# preamp.net
KiCad netlist of a schematic drawn in EAGLE
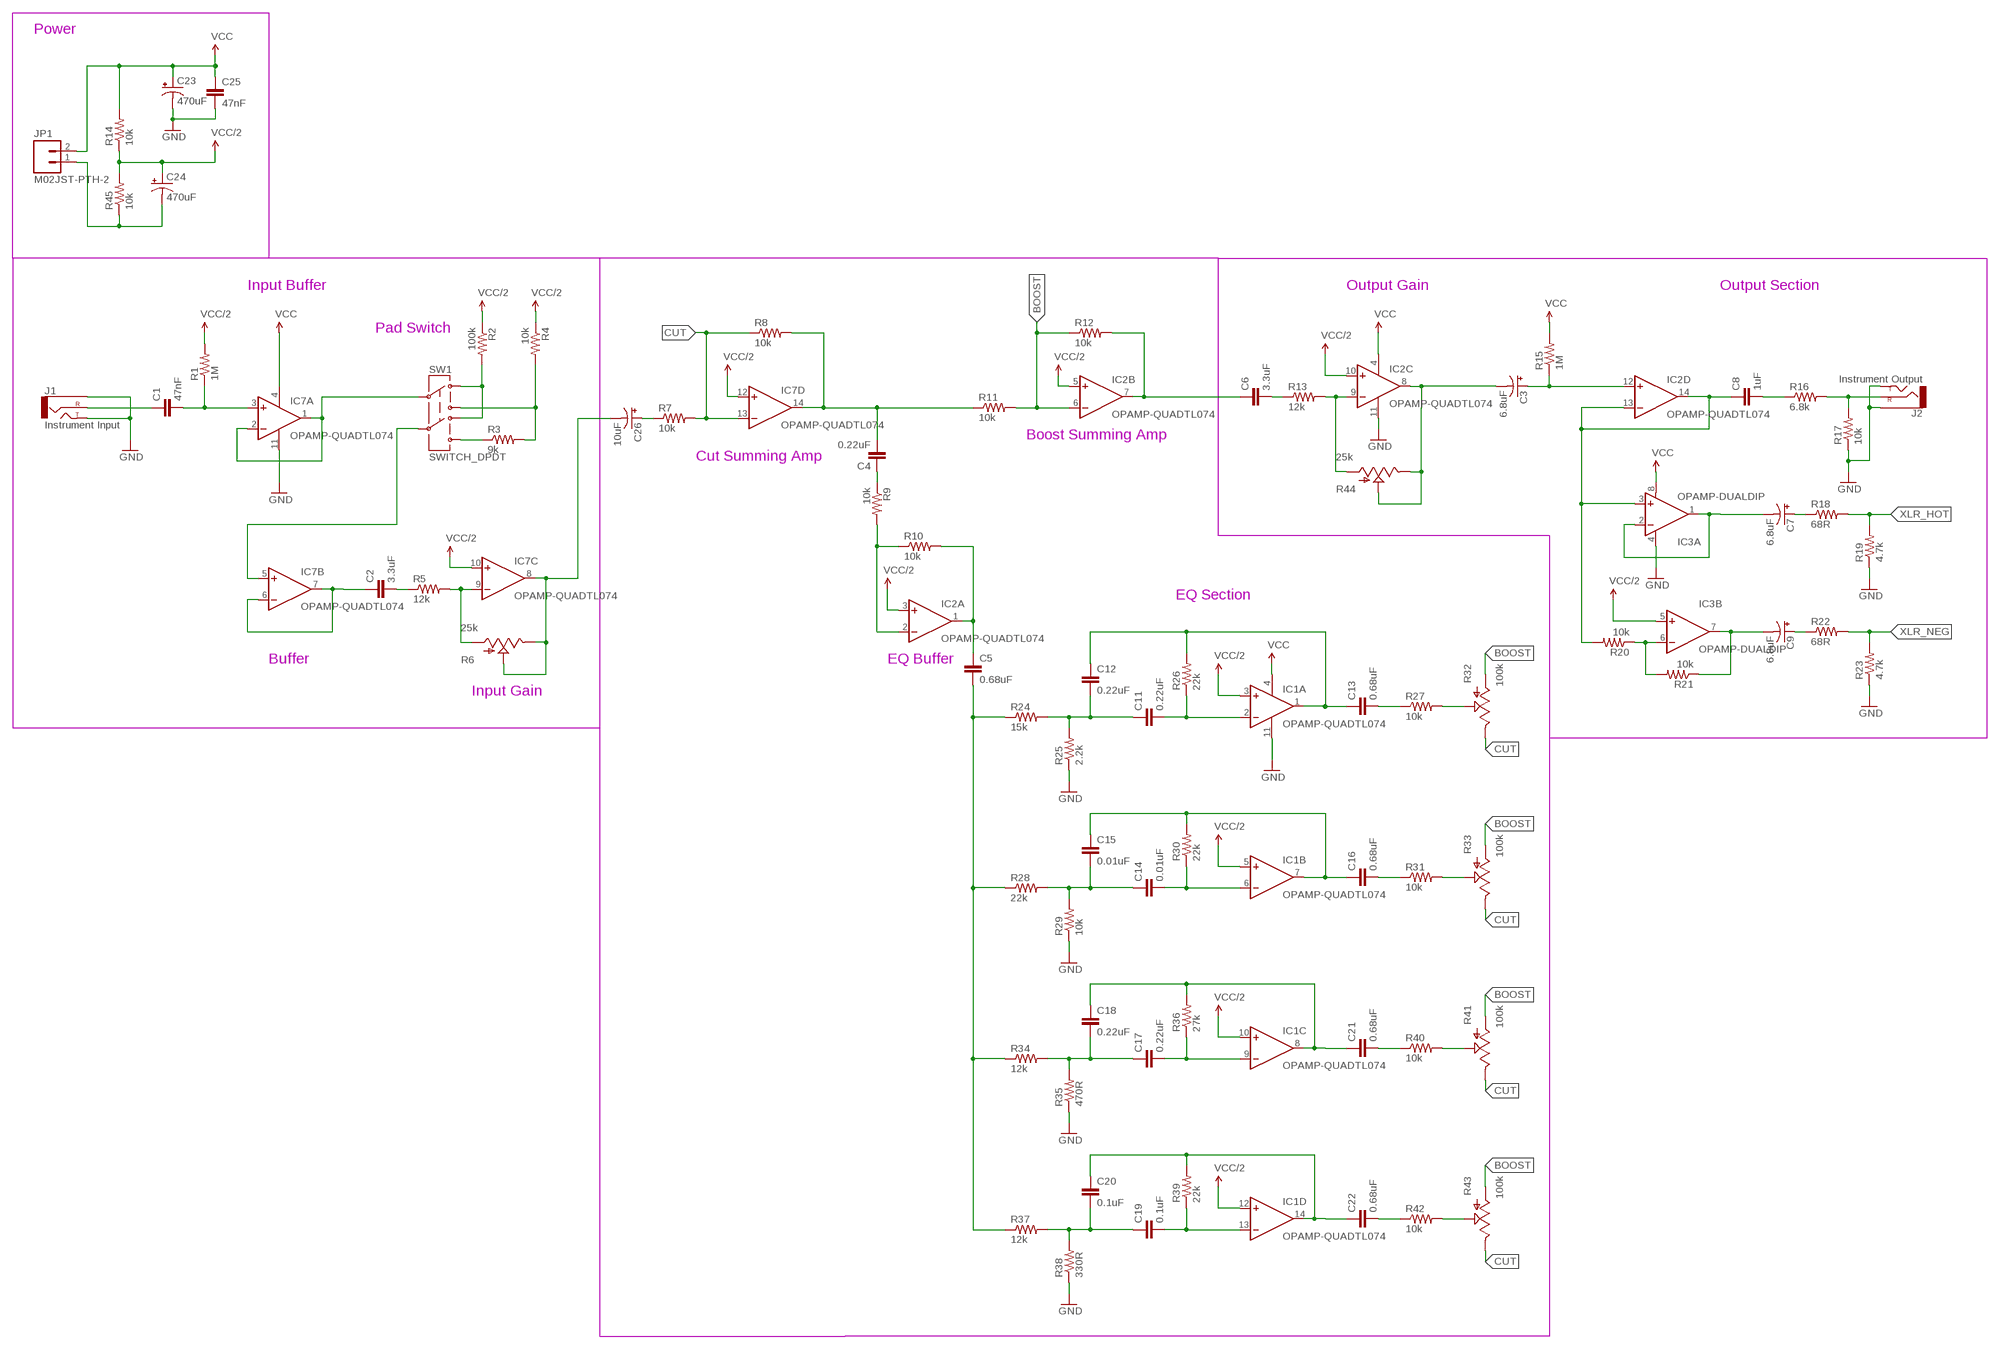
[diagram p0: schematic, sheet 1]

(export (version "E")
  (design (tool "Eeschema 10.0.6"))
  (components
    (comp (ref "C1")
      (value "47nF")
      (footprint "eagle-import:CAP-5MM")
      (fields (field (name "PARTNO") "FK28X7R1H473K"))
      (libsource (lib "eagle-import") (part "CAP"))
    )
    (comp (ref "C2")
      (value "3.3uF")
      (footprint "eagle-import:CAP-5MM")
      (fields (field (name "PARTNO") "FK28X5R1A335K"))
      (libsource (lib "eagle-import") (part "CAP"))
    )
    (comp (ref "C3")
      (value "6.8uF")
      (footprint "eagle-import:CPOL-RADIAL-10UF-25V")
      (fields (field (name "PARTNO") "ESH685M063AC3AA"))
      (libsource (lib "eagle-import") (part "CAP_POLPTH2"))
    )
    (comp (ref "C4")
      (value "0.22uF")
      (footprint "eagle-import:CAP-5MM")
      (fields (field (name "PARTNO") "FK28X7R1C224K"))
      (libsource (lib "eagle-import") (part "CAP"))
    )
    (comp (ref "C5")
      (value "0.68uF")
      (footprint "eagle-import:CAP-5MM")
      (fields (field (name "PARTNO") "FK28X5R1A684K"))
      (libsource (lib "eagle-import") (part "CAP"))
    )
    (comp (ref "C6")
      (value "3.3uF")
      (footprint "eagle-import:CAP-5MM")
      (fields (field (name "PARTNO") "FK28X5R1A335K"))
      (libsource (lib "eagle-import") (part "CAP"))
    )
    (comp (ref "C7")
      (value "6.8uF")
      (footprint "eagle-import:CPOL-RADIAL-10UF-25V")
      (fields (field (name "PARTNO") "ESH685M063AC3AA"))
      (libsource (lib "eagle-import") (part "CAP_POLPTH2"))
    )
    (comp (ref "C8")
      (value "1uF")
      (footprint "eagle-import:CAP-5MM")
      (libsource (lib "eagle-import") (part "CAP"))
    )
    (comp (ref "C9")
      (value "6.8uF")
      (footprint "eagle-import:CPOL-RADIAL-10UF-25V")
      (fields (field (name "PARTNO") "ESH685M063AC3AA"))
      (libsource (lib "eagle-import") (part "CAP_POLPTH2"))
    )
    (comp (ref "C11")
      (value "0.22uF")
      (footprint "eagle-import:CAP-5MM")
      (fields (field (name "PARTNO") "FK28X7R1C224K"))
      (libsource (lib "eagle-import") (part "CAP"))
    )
    (comp (ref "C12")
      (value "0.22uF")
      (footprint "eagle-import:CAP-5MM")
      (fields (field (name "PARTNO") "FK28X7R1C224K"))
      (libsource (lib "eagle-import") (part "CAP"))
    )
    (comp (ref "C13")
      (value "0.68uF")
      (footprint "eagle-import:CAP-5MM")
      (fields (field (name "PARTNO") "FK28X5R1A684K"))
      (libsource (lib "eagle-import") (part "CAP"))
    )
    (comp (ref "C14")
      (value "0.01uF")
      (footprint "eagle-import:CAP-5MM")
      (libsource (lib "eagle-import") (part "CAP"))
    )
    (comp (ref "C15")
      (value "0.01uF")
      (footprint "eagle-import:CAP-5MM")
      (libsource (lib "eagle-import") (part "CAP"))
    )
    (comp (ref "C16")
      (value "0.68uF")
      (footprint "eagle-import:CAP-5MM")
      (fields (field (name "PARTNO") "FK28X5R1A684K"))
      (libsource (lib "eagle-import") (part "CAP"))
    )
    (comp (ref "C17")
      (value "0.22uF")
      (footprint "eagle-import:CAP-5MM")
      (fields (field (name "PARTNO") "FK28X7R1C224K"))
      (libsource (lib "eagle-import") (part "CAP"))
    )
    (comp (ref "C18")
      (value "0.22uF")
      (footprint "eagle-import:CAP-5MM")
      (fields (field (name "PARTNO") "FK28X7R1C224K"))
      (libsource (lib "eagle-import") (part "CAP"))
    )
    (comp (ref "C19")
      (value "0.1uF")
      (footprint "eagle-import:CAP-5MM")
      (libsource (lib "eagle-import") (part "CAP"))
    )
    (comp (ref "C20")
      (value "0.1uF")
      (footprint "eagle-import:CAP-5MM")
      (libsource (lib "eagle-import") (part "CAP"))
    )
    (comp (ref "C21")
      (value "0.68uF")
      (footprint "eagle-import:CAP-5MM")
      (fields (field (name "PARTNO") "FK28X5R1A684K"))
      (libsource (lib "eagle-import") (part "CAP"))
    )
    (comp (ref "C22")
      (value "0.68uF")
      (footprint "eagle-import:CAP-5MM")
      (fields (field (name "PARTNO") "FK28X5R1A684K"))
      (libsource (lib "eagle-import") (part "CAP"))
    )
    (comp (ref "C23")
      (value "470uF")
      (footprint "eagle-import:CPOL-RADIAL-100UF-25V")
      (libsource (lib "eagle-import") (part "SparkFun-Passives_CAP_POLPTH1"))
    )
    (comp (ref "C24")
      (value "470uF")
      (footprint "eagle-import:CPOL-RADIAL-100UF-25V")
      (libsource (lib "eagle-import") (part "SparkFun-Passives_CAP_POLPTH1"))
    )
    (comp (ref "C25")
      (value "47nF")
      (footprint "eagle-import:CAP-5MM")
      (fields (field (name "PARTNO") "FK28X7R1H473K"))
      (libsource (lib "eagle-import") (part "CAP"))
    )
    (comp (ref "C26")
      (value "10uF")
      (footprint "eagle-import:CPOL-RADIAL-10UF-25V")
      (libsource (lib "eagle-import") (part "CAP_POLPTH2"))
    )
    (comp (ref "IC1")
      (value "OPAMP-QUADTL074")
      (footprint "eagle-import:DIP14")
      (fields (field (name "PARTNO") "TL074CN"))
      (libsource (lib "eagle-import") (part "OPAMP-QUADTL074"))
    )
    (comp (ref "IC2")
      (value "OPAMP-QUADTL074")
      (footprint "eagle-import:DIP14")
      (fields (field (name "PARTNO") "TL074CN"))
      (libsource (lib "eagle-import") (part "OPAMP-QUADTL074"))
    )
    (comp (ref "IC3")
      (value "OPAMP-DUALDIP")
      (footprint "eagle-import:DIP08")
      (fields (field (name "PARTNO") "TL072IP"))
      (libsource (lib "eagle-import") (part "OPAMP-DUALDIP"))
    )
    (comp (ref "IC7")
      (value "OPAMP-QUADTL074")
      (footprint "eagle-import:DIP14")
      (fields (field (name "PARTNO") "TL074CN"))
      (libsource (lib "eagle-import") (part "OPAMP-QUADTL074"))
    )
    (comp (ref "J1")
      (value "Instrument Input")
      (footprint "eagle-import:AUDIO-JACK-RA49B12B")
      (libsource (lib "eagle-import") (part "AUDIO-JACK"))
    )
    (comp (ref "J2")
      (value "Instrument Output")
      (footprint "eagle-import:AUDIO-JACK-RA49B12B")
      (libsource (lib "eagle-import") (part "AUDIO-JACK"))
    )
    (comp (ref "JP1")
      (value "M02JST-PTH-2")
      (footprint "eagle-import:JST-2-PTH")
      (libsource (lib "eagle-import") (part "M02JST-PTH-2"))
    )
    (comp (ref "R1")
      (value "1M")
      (footprint "eagle-import:AXIAL-0.4")
      (fields (field (name "PARTNO") "CF14JT1M00"))
      (libsource (lib "eagle-import") (part "RESISTORPTH-1/4W"))
    )
    (comp (ref "R2")
      (value "100k")
      (footprint "eagle-import:AXIAL-0.4")
      (fields (field (name "PARTNO") "CF14JT100K"))
      (libsource (lib "eagle-import") (part "RESISTORPTH-1/4W"))
    )
    (comp (ref "R3")
      (value "9k")
      (footprint "eagle-import:AXIAL-0.4")
      (fields (field (name "PARTNO") "CF14JT9K10"))
      (libsource (lib "eagle-import") (part "RESISTORPTH-1/4W"))
    )
    (comp (ref "R4")
      (value "10k")
      (footprint "eagle-import:AXIAL-0.4")
      (fields (field (name "PARTNO") "CF14JT10K0"))
      (libsource (lib "eagle-import") (part "RESISTORPTH-1/4W"))
    )
    (comp (ref "R5")
      (value "12k")
      (footprint "eagle-import:AXIAL-0.4")
      (fields (field (name "PARTNO") "CF14JT12K0"))
      (libsource (lib "eagle-import") (part "RESISTORPTH-1/4W"))
    )
    (comp (ref "R6")
      (value "25k")
      (footprint "eagle-import:POTENTIOMETER-EVUE2A")
      (fields (field (name "PARTNO") "EVU-E2AF25D24"))
      (libsource (lib "eagle-import") (part "POTPANA"))
    )
    (comp (ref "R7")
      (value "10k")
      (footprint "eagle-import:AXIAL-0.4")
      (fields (field (name "PARTNO") "CF14JT10K0"))
      (libsource (lib "eagle-import") (part "RESISTORPTH-1/4W"))
    )
    (comp (ref "R8")
      (value "10k")
      (footprint "eagle-import:AXIAL-0.4")
      (fields (field (name "PARTNO") "CF14JT10K0"))
      (libsource (lib "eagle-import") (part "RESISTORPTH-1/4W"))
    )
    (comp (ref "R9")
      (value "10k")
      (footprint "eagle-import:AXIAL-0.4")
      (fields (field (name "PARTNO") "CF14JT10K0"))
      (libsource (lib "eagle-import") (part "RESISTORPTH-1/4W"))
    )
    (comp (ref "R10")
      (value "10k")
      (footprint "eagle-import:AXIAL-0.4")
      (fields (field (name "PARTNO") "CF14JT10K0"))
      (libsource (lib "eagle-import") (part "RESISTORPTH-1/4W"))
    )
    (comp (ref "R11")
      (value "10k")
      (footprint "eagle-import:AXIAL-0.4")
      (fields (field (name "PARTNO") "CF14JT10K0"))
      (libsource (lib "eagle-import") (part "RESISTORPTH-1/4W"))
    )
    (comp (ref "R12")
      (value "10k")
      (footprint "eagle-import:AXIAL-0.4")
      (fields (field (name "PARTNO") "CF14JT10K0"))
      (libsource (lib "eagle-import") (part "RESISTORPTH-1/4W"))
    )
    (comp (ref "R13")
      (value "12k")
      (footprint "eagle-import:AXIAL-0.4")
      (fields (field (name "PARTNO") "CF14JT12K0"))
      (libsource (lib "eagle-import") (part "RESISTORPTH-1/4W"))
    )
    (comp (ref "R14")
      (value "10k")
      (footprint "eagle-import:AXIAL-0.4")
      (fields (field (name "PARTNO") "CF14JT10K0"))
      (libsource (lib "eagle-import") (part "RESISTORPTH-1/4W"))
    )
    (comp (ref "R15")
      (value "1M")
      (footprint "eagle-import:AXIAL-0.4")
      (fields (field (name "PARTNO") "CF14JT1M00"))
      (libsource (lib "eagle-import") (part "RESISTORPTH-1/4W"))
    )
    (comp (ref "R16")
      (value "6.8k")
      (footprint "eagle-import:AXIAL-0.4")
      (fields (field (name "PARTNO") "CF14JT6K80"))
      (libsource (lib "eagle-import") (part "RESISTORPTH-1/4W"))
    )
    (comp (ref "R17")
      (value "10k")
      (footprint "eagle-import:AXIAL-0.4")
      (fields (field (name "PARTNO") "CF14JT10K0"))
      (libsource (lib "eagle-import") (part "RESISTORPTH-1/4W"))
    )
    (comp (ref "R18")
      (value "68R")
      (footprint "eagle-import:AXIAL-0.4")
      (fields (field (name "PARTNO") "CF14JT68R0"))
      (libsource (lib "eagle-import") (part "RESISTORPTH-1/4W"))
    )
    (comp (ref "R19")
      (value "4.7k")
      (footprint "eagle-import:AXIAL-0.4")
      (fields (field (name "PARTNO") "CF14JT4K70"))
      (libsource (lib "eagle-import") (part "RESISTORPTH-1/4W"))
    )
    (comp (ref "R20")
      (value "10k")
      (footprint "eagle-import:AXIAL-0.4")
      (fields (field (name "PARTNO") "CF14JT10K0"))
      (libsource (lib "eagle-import") (part "RESISTORPTH-1/4W"))
    )
    (comp (ref "R21")
      (value "10k")
      (footprint "eagle-import:AXIAL-0.4")
      (fields (field (name "PARTNO") "CF14JT10K0"))
      (libsource (lib "eagle-import") (part "RESISTORPTH-1/4W"))
    )
    (comp (ref "R22")
      (value "68R")
      (footprint "eagle-import:AXIAL-0.4")
      (fields (field (name "PARTNO") "CF14JT68R0"))
      (libsource (lib "eagle-import") (part "RESISTORPTH-1/4W"))
    )
    (comp (ref "R23")
      (value "4.7k")
      (footprint "eagle-import:AXIAL-0.4")
      (fields (field (name "PARTNO") "CF14JT4K70"))
      (libsource (lib "eagle-import") (part "RESISTORPTH-1/4W"))
    )
    (comp (ref "R24")
      (value "15k")
      (footprint "eagle-import:AXIAL-0.4")
      (fields (field (name "PARTNO") "CF14JT15K0"))
      (libsource (lib "eagle-import") (part "RESISTORPTH-1/4W"))
    )
    (comp (ref "R25")
      (value "2.2k")
      (footprint "eagle-import:AXIAL-0.4")
      (fields (field (name "PARTNO") "CF14JT2K20"))
      (libsource (lib "eagle-import") (part "RESISTORPTH-1/4W"))
    )
    (comp (ref "R26")
      (value "22k")
      (footprint "eagle-import:AXIAL-0.4")
      (fields (field (name "PARTNO") "CF14JT22K0"))
      (libsource (lib "eagle-import") (part "RESISTORPTH-1/4W"))
    )
    (comp (ref "R27")
      (value "10k")
      (footprint "eagle-import:AXIAL-0.4")
      (fields (field (name "PARTNO") "CF14JT10K0"))
      (libsource (lib "eagle-import") (part "RESISTORPTH-1/4W"))
    )
    (comp (ref "R28")
      (value "22k")
      (footprint "eagle-import:AXIAL-0.4")
      (fields (field (name "PARTNO") "CF14JT22K0"))
      (libsource (lib "eagle-import") (part "RESISTORPTH-1/4W"))
    )
    (comp (ref "R29")
      (value "10k")
      (footprint "eagle-import:AXIAL-0.4")
      (fields (field (name "PARTNO") "CF14JT10K0"))
      (libsource (lib "eagle-import") (part "RESISTORPTH-1/4W"))
    )
    (comp (ref "R30")
      (value "22k")
      (footprint "eagle-import:AXIAL-0.4")
      (fields (field (name "PARTNO") "CF14JT22K0"))
      (libsource (lib "eagle-import") (part "RESISTORPTH-1/4W"))
    )
    (comp (ref "R31")
      (value "10k")
      (footprint "eagle-import:AXIAL-0.4")
      (fields (field (name "PARTNO") "CF14JT10K0"))
      (libsource (lib "eagle-import") (part "RESISTORPTH-1/4W"))
    )
    (comp (ref "R32")
      (value "100k")
      (footprint "eagle-import:POTENTIOMETER-PTV09A-2020F-B104")
      (fields (field (name "PARTNO") "PTV09A-2020F-B104"))
      (libsource (lib "eagle-import") (part "POTBOURNS"))
    )
    (comp (ref "R33")
      (value "100k")
      (footprint "eagle-import:POTENTIOMETER-PTV09A-2020F-B104")
      (fields (field (name "PARTNO") "PTV09A-2020F-B104"))
      (libsource (lib "eagle-import") (part "POTBOURNS"))
    )
    (comp (ref "R34")
      (value "12k")
      (footprint "eagle-import:AXIAL-0.4")
      (fields (field (name "PARTNO") "CF14JT12K0"))
      (libsource (lib "eagle-import") (part "RESISTORPTH-1/4W"))
    )
    (comp (ref "R35")
      (value "470R")
      (footprint "eagle-import:AXIAL-0.4")
      (libsource (lib "eagle-import") (part "RESISTORPTH-1/4W"))
    )
    (comp (ref "R36")
      (value "27k")
      (footprint "eagle-import:AXIAL-0.4")
      (libsource (lib "eagle-import") (part "RESISTORPTH-1/4W"))
    )
    (comp (ref "R37")
      (value "12k")
      (footprint "eagle-import:AXIAL-0.4")
      (fields (field (name "PARTNO") "CF14JT12K0"))
      (libsource (lib "eagle-import") (part "RESISTORPTH-1/4W"))
    )
    (comp (ref "R38")
      (value "330R")
      (footprint "eagle-import:AXIAL-0.4")
      (libsource (lib "eagle-import") (part "RESISTORPTH-1/4W"))
    )
    (comp (ref "R39")
      (value "22k")
      (footprint "eagle-import:AXIAL-0.4")
      (fields (field (name "PARTNO") "CF14JT22K0"))
      (libsource (lib "eagle-import") (part "RESISTORPTH-1/4W"))
    )
    (comp (ref "R40")
      (value "10k")
      (footprint "eagle-import:AXIAL-0.4")
      (fields (field (name "PARTNO") "CF14JT10K0"))
      (libsource (lib "eagle-import") (part "RESISTORPTH-1/4W"))
    )
    (comp (ref "R41")
      (value "100k")
      (footprint "eagle-import:POTENTIOMETER-PTV09A-2020F-B104")
      (fields (field (name "PARTNO") "PTV09A-2020F-B104"))
      (libsource (lib "eagle-import") (part "POTBOURNS"))
    )
    (comp (ref "R42")
      (value "10k")
      (footprint "eagle-import:AXIAL-0.4")
      (fields (field (name "PARTNO") "CF14JT10K0"))
      (libsource (lib "eagle-import") (part "RESISTORPTH-1/4W"))
    )
    (comp (ref "R43")
      (value "100k")
      (footprint "eagle-import:POTENTIOMETER-PTV09A-2020F-B104")
      (fields (field (name "PARTNO") "PTV09A-2020F-B104"))
      (libsource (lib "eagle-import") (part "POTBOURNS"))
    )
    (comp (ref "R44")
      (value "25k")
      (footprint "eagle-import:POTENTIOMETER-EVUE2A")
      (fields (field (name "PARTNO") "EVU-E2AF25D24"))
      (libsource (lib "eagle-import") (part "POTPANA"))
    )
    (comp (ref "R45")
      (value "10k")
      (footprint "eagle-import:AXIAL-0.4")
      (fields (field (name "PARTNO") "CF14JT10K0"))
      (libsource (lib "eagle-import") (part "RESISTORPTH-1/4W"))
    )
    (comp (ref "SW1")
      (value "SWITCH_DPDT")
      (footprint "eagle-import:SWITCH-EG2211")
      (libsource (lib "eagle-import") (part "SWITCH_DPDT"))
    )
  )
  (nets
    (net (code "1") (name "BOOST") (class "Default")
      (node (ref "IC2") (pin "6") (pinfunction "IN-_6") (pintype "input"))
      (node (ref "R11") (pin "P$2") (pinfunction "2_P$2") (pintype "passive"))
      (node (ref "R12") (pin "P$1") (pinfunction "1_P$1") (pintype "passive"))
      (node (ref "R32") (pin "3") (pinfunction "A_3") (pintype "passive"))
      (node (ref "R33") (pin "3") (pinfunction "A_3") (pintype "passive"))
      (node (ref "R41") (pin "3") (pinfunction "A_3") (pintype "passive"))
      (node (ref "R43") (pin "3") (pinfunction "A_3") (pintype "passive"))
    )
    (net (code "2") (name "CUT") (class "Default")
      (node (ref "IC7") (pin "13") (pinfunction "IN-_13") (pintype "input"))
      (node (ref "R32") (pin "1") (pinfunction "E_1") (pintype "passive"))
      (node (ref "R33") (pin "1") (pinfunction "E_1") (pintype "passive"))
      (node (ref "R41") (pin "1") (pinfunction "E_1") (pintype "passive"))
      (node (ref "R43") (pin "1") (pinfunction "E_1") (pintype "passive"))
      (node (ref "R7") (pin "P$2") (pinfunction "2_P$2") (pintype "passive"))
      (node (ref "R8") (pin "P$1") (pinfunction "1_P$1") (pintype "passive"))
    )
    (net (code "3") (name "GND") (class "Default")
      (node (ref "C23") (pin "2") (pinfunction "-_2") (pintype "passive"))
      (node (ref "C25") (pin "2") (pinfunction "2_2") (pintype "passive"))
      (node (ref "IC1") (pin "11") (pinfunction "VEE_11") (pintype "power_in"))
      (node (ref "IC2") (pin "11") (pinfunction "VEE_11") (pintype "power_in"))
      (node (ref "IC3") (pin "4") (pinfunction "V-_4") (pintype "power_in"))
      (node (ref "IC7") (pin "11") (pinfunction "VEE_11") (pintype "power_in"))
      (node (ref "J1") (pin "S") (pinfunction "SLEEVE_S") (pintype "bidirectional"))
      (node (ref "J1") (pin "T") (pinfunction "TIP_T") (pintype "bidirectional"))
      (node (ref "J2") (pin "S") (pinfunction "SLEEVE_S") (pintype "bidirectional"))
      (node (ref "J2") (pin "T") (pinfunction "TIP_T") (pintype "bidirectional"))
      (node (ref "R17") (pin "P$1") (pinfunction "1_P$1") (pintype "passive"))
      (node (ref "R19") (pin "P$1") (pinfunction "1_P$1") (pintype "passive"))
      (node (ref "R23") (pin "P$1") (pinfunction "1_P$1") (pintype "passive"))
      (node (ref "R25") (pin "P$1") (pinfunction "1_P$1") (pintype "passive"))
      (node (ref "R29") (pin "P$1") (pinfunction "1_P$1") (pintype "passive"))
      (node (ref "R35") (pin "P$1") (pinfunction "1_P$1") (pintype "passive"))
      (node (ref "R38") (pin "P$1") (pinfunction "1_P$1") (pintype "passive"))
    )
    (net (code "4") (name "Net-(C3-+)") (class "Default")
      (node (ref "C3") (pin "1") (pinfunction "+_1") (pintype "passive"))
      (node (ref "IC2") (pin "12") (pinfunction "IN+_12") (pintype "input"))
      (node (ref "R15") (pin "P$1") (pinfunction "1_P$1") (pintype "passive"))
    )
    (net (code "5") (name "Net-(C3--)") (class "Default")
      (node (ref "C3") (pin "2") (pinfunction "-_2") (pintype "passive"))
      (node (ref "IC2") (pin "8") (pinfunction "OUT_8") (pintype "output"))
      (node (ref "R44") (pin "2") (pinfunction "S_2") (pintype "passive"))
      (node (ref "R44") (pin "3") (pinfunction "E_3") (pintype "passive"))
    )
    (net (code "6") (name "Net-(C7-+)") (class "Default")
      (node (ref "C7") (pin "1") (pinfunction "+_1") (pintype "passive"))
      (node (ref "R18") (pin "P$1") (pinfunction "1_P$1") (pintype "passive"))
    )
    (net (code "7") (name "Net-(C7--)") (class "Default")
      (node (ref "C7") (pin "2") (pinfunction "-_2") (pintype "passive"))
      (node (ref "IC3") (pin "1") (pinfunction "OUT_1") (pintype "output"))
      (node (ref "IC3") (pin "2") (pinfunction "-IN_2") (pintype "input"))
    )
    (net (code "8") (name "Net-(C9-+)") (class "Default")
      (node (ref "C9") (pin "1") (pinfunction "+_1") (pintype "passive"))
      (node (ref "R22") (pin "P$1") (pinfunction "1_P$1") (pintype "passive"))
    )
    (net (code "9") (name "Net-(C9--)") (class "Default")
      (node (ref "C9") (pin "2") (pinfunction "-_2") (pintype "passive"))
      (node (ref "IC3") (pin "7") (pinfunction "OUT_7") (pintype "output"))
      (node (ref "R21") (pin "P$1") (pinfunction "1_P$1") (pintype "passive"))
    )
    (net (code "10") (name "Net-(C24--)") (class "Default")
      (node (ref "C24") (pin "2") (pinfunction "-_2") (pintype "passive"))
      (node (ref "JP1") (pin "1") (pinfunction "1_1") (pintype "passive"))
      (node (ref "R45") (pin "P$1") (pinfunction "1_P$1") (pintype "passive"))
    )
    (net (code "11") (name "Net-(C26-+)") (class "Default")
      (node (ref "C26") (pin "1") (pinfunction "+_1") (pintype "passive"))
      (node (ref "R7") (pin "P$1") (pinfunction "1_P$1") (pintype "passive"))
    )
    (net (code "12") (name "Net-(C26--)") (class "Default")
      (node (ref "C26") (pin "2") (pinfunction "-_2") (pintype "passive"))
      (node (ref "IC7") (pin "8") (pinfunction "OUT_8") (pintype "output"))
      (node (ref "R6") (pin "2") (pinfunction "S_2") (pintype "passive"))
      (node (ref "R6") (pin "3") (pinfunction "E_3") (pintype "passive"))
    )
    (net (code "13") (name "Net-(IC1A-IN-)") (class "Default")
      (node (ref "C11") (pin "2") (pinfunction "2_2") (pintype "passive"))
      (node (ref "IC1") (pin "2") (pinfunction "IN-_2") (pintype "input"))
      (node (ref "R26") (pin "P$1") (pinfunction "1_P$1") (pintype "passive"))
    )
    (net (code "14") (name "Net-(IC1A-OUT)") (class "Default")
      (node (ref "C12") (pin "1") (pinfunction "1_1") (pintype "passive"))
      (node (ref "C13") (pin "1") (pinfunction "1_1") (pintype "passive"))
      (node (ref "IC1") (pin "1") (pinfunction "OUT_1") (pintype "output"))
      (node (ref "R26") (pin "P$2") (pinfunction "2_P$2") (pintype "passive"))
    )
    (net (code "15") (name "Net-(IC1B-IN-)") (class "Default")
      (node (ref "C14") (pin "2") (pinfunction "2_2") (pintype "passive"))
      (node (ref "IC1") (pin "6") (pinfunction "IN-_6") (pintype "input"))
      (node (ref "R30") (pin "P$1") (pinfunction "1_P$1") (pintype "passive"))
    )
    (net (code "16") (name "Net-(IC1B-OUT)") (class "Default")
      (node (ref "C15") (pin "1") (pinfunction "1_1") (pintype "passive"))
      (node (ref "C16") (pin "1") (pinfunction "1_1") (pintype "passive"))
      (node (ref "IC1") (pin "7") (pinfunction "OUT_7") (pintype "output"))
      (node (ref "R30") (pin "P$2") (pinfunction "2_P$2") (pintype "passive"))
    )
    (net (code "17") (name "Net-(IC1C-IN-)") (class "Default")
      (node (ref "C17") (pin "2") (pinfunction "2_2") (pintype "passive"))
      (node (ref "IC1") (pin "9") (pinfunction "IN-_9") (pintype "input"))
      (node (ref "R36") (pin "P$1") (pinfunction "1_P$1") (pintype "passive"))
    )
    (net (code "18") (name "Net-(IC1C-OUT)") (class "Default")
      (node (ref "C18") (pin "1") (pinfunction "1_1") (pintype "passive"))
      (node (ref "C21") (pin "1") (pinfunction "1_1") (pintype "passive"))
      (node (ref "IC1") (pin "8") (pinfunction "OUT_8") (pintype "output"))
      (node (ref "R36") (pin "P$2") (pinfunction "2_P$2") (pintype "passive"))
    )
    (net (code "19") (name "Net-(IC1D-IN-)") (class "Default")
      (node (ref "C19") (pin "2") (pinfunction "2_2") (pintype "passive"))
      (node (ref "IC1") (pin "13") (pinfunction "IN-_13") (pintype "input"))
      (node (ref "R39") (pin "P$1") (pinfunction "1_P$1") (pintype "passive"))
    )
    (net (code "20") (name "Net-(IC1D-OUT)") (class "Default")
      (node (ref "C20") (pin "1") (pinfunction "1_1") (pintype "passive"))
      (node (ref "C22") (pin "1") (pinfunction "1_1") (pintype "passive"))
      (node (ref "IC1") (pin "14") (pinfunction "OUT_14") (pintype "output"))
      (node (ref "R39") (pin "P$2") (pinfunction "2_P$2") (pintype "passive"))
    )
    (net (code "21") (name "Net-(IC2A-IN-)") (class "Default")
      (node (ref "IC2") (pin "2") (pinfunction "IN-_2") (pintype "input"))
      (node (ref "R10") (pin "P$1") (pinfunction "1_P$1") (pintype "passive"))
      (node (ref "R9") (pin "P$2") (pinfunction "2_P$2") (pintype "passive"))
    )
    (net (code "22") (name "Net-(IC2A-OUT)") (class "Default")
      (node (ref "C5") (pin "1") (pinfunction "1_1") (pintype "passive"))
      (node (ref "IC2") (pin "1") (pinfunction "OUT_1") (pintype "output"))
      (node (ref "R10") (pin "P$2") (pinfunction "2_P$2") (pintype "passive"))
    )
    (net (code "23") (name "Net-(IC2B-OUT)") (class "Default")
      (node (ref "C6") (pin "1") (pinfunction "1_1") (pintype "passive"))
      (node (ref "IC2") (pin "7") (pinfunction "OUT_7") (pintype "output"))
      (node (ref "R12") (pin "P$2") (pinfunction "2_P$2") (pintype "passive"))
    )
    (net (code "24") (name "Net-(IC2C-IN-)") (class "Default")
      (node (ref "IC2") (pin "9") (pinfunction "IN-_9") (pintype "input"))
      (node (ref "R13") (pin "P$2") (pinfunction "2_P$2") (pintype "passive"))
      (node (ref "R44") (pin "1") (pinfunction "A_1") (pintype "passive"))
    )
    (net (code "25") (name "Net-(IC2D-IN-)") (class "Default")
      (node (ref "C8") (pin "1") (pinfunction "1_1") (pintype "passive"))
      (node (ref "IC2") (pin "13") (pinfunction "IN-_13") (pintype "input"))
      (node (ref "IC2") (pin "14") (pinfunction "OUT_14") (pintype "output"))
      (node (ref "IC3") (pin "3") (pinfunction "+IN_3") (pintype "input"))
      (node (ref "R20") (pin "P$2") (pinfunction "2_P$2") (pintype "passive"))
    )
    (net (code "26") (name "Net-(IC3B--IN)") (class "Default")
      (node (ref "IC3") (pin "6") (pinfunction "-IN_6") (pintype "input"))
      (node (ref "R20") (pin "P$1") (pinfunction "1_P$1") (pintype "passive"))
      (node (ref "R21") (pin "P$2") (pinfunction "2_P$2") (pintype "passive"))
    )
    (net (code "27") (name "Net-(IC7A-IN+)") (class "Default")
      (node (ref "C1") (pin "2") (pinfunction "2_2") (pintype "passive"))
      (node (ref "IC7") (pin "3") (pinfunction "IN+_3") (pintype "input"))
      (node (ref "R1") (pin "P$1") (pinfunction "1_P$1") (pintype "passive"))
    )
    (net (code "28") (name "Net-(IC7A-IN-)") (class "Default")
      (node (ref "IC7") (pin "1") (pinfunction "OUT_1") (pintype "output"))
      (node (ref "IC7") (pin "2") (pinfunction "IN-_2") (pintype "input"))
      (node (ref "SW1") (pin "C1") (pinfunction "C1_C1") (pintype "bidirectional"))
    )
    (net (code "29") (name "Net-(IC7B-IN+)") (class "Default")
      (node (ref "IC7") (pin "5") (pinfunction "IN+_5") (pintype "input"))
      (node (ref "SW1") (pin "C2") (pinfunction "C2_C2") (pintype "bidirectional"))
    )
    (net (code "30") (name "Net-(IC7B-IN-)") (class "Default")
      (node (ref "C2") (pin "1") (pinfunction "1_1") (pintype "passive"))
      (node (ref "IC7") (pin "6") (pinfunction "IN-_6") (pintype "input"))
      (node (ref "IC7") (pin "7") (pinfunction "OUT_7") (pintype "output"))
    )
    (net (code "31") (name "Net-(IC7C-IN-)") (class "Default")
      (node (ref "IC7") (pin "9") (pinfunction "IN-_9") (pintype "input"))
      (node (ref "R5") (pin "P$2") (pinfunction "2_P$2") (pintype "passive"))
      (node (ref "R6") (pin "1") (pinfunction "A_1") (pintype "passive"))
    )
    (net (code "32") (name "Net-(IC7D-OUT)") (class "Default")
      (node (ref "C4") (pin "2") (pinfunction "2_2") (pintype "passive"))
      (node (ref "IC7") (pin "14") (pinfunction "OUT_14") (pintype "output"))
      (node (ref "R11") (pin "P$1") (pinfunction "1_P$1") (pintype "passive"))
      (node (ref "R8") (pin "P$2") (pinfunction "2_P$2") (pintype "passive"))
    )
    (net (code "33") (name "Net-(J1-RING)") (class "Default")
      (node (ref "C1") (pin "1") (pinfunction "1_1") (pintype "passive"))
      (node (ref "J1") (pin "R") (pinfunction "RING_R") (pintype "bidirectional"))
    )
    (net (code "34") (name "Net-(J2-RING)") (class "Default")
      (node (ref "J2") (pin "R") (pinfunction "RING_R") (pintype "bidirectional"))
      (node (ref "R16") (pin "P$2") (pinfunction "2_P$2") (pintype "passive"))
      (node (ref "R17") (pin "P$2") (pinfunction "2_P$2") (pintype "passive"))
    )
    (net (code "35") (name "Net-(R2-2)") (class "Default")
      (node (ref "R2") (pin "P$2") (pinfunction "2_P$2") (pintype "passive"))
      (node (ref "SW1") (pin "L1") (pinfunction "L1_L1") (pintype "bidirectional"))
      (node (ref "SW1") (pin "L2") (pinfunction "L2_L2") (pintype "bidirectional"))
    )
    (net (code "36") (name "Net-(R3-1)") (class "Default")
      (node (ref "R3") (pin "P$1") (pinfunction "1_P$1") (pintype "passive"))
      (node (ref "SW1") (pin "R2") (pinfunction "R2_R2") (pintype "bidirectional"))
    )
    (net (code "37") (name "Net-(R3-2)") (class "Default")
      (node (ref "R3") (pin "P$2") (pinfunction "2_P$2") (pintype "passive"))
      (node (ref "R4") (pin "P$2") (pinfunction "2_P$2") (pintype "passive"))
      (node (ref "SW1") (pin "R1") (pinfunction "R1_R1") (pintype "bidirectional"))
    )
    (net (code "38") (name "Net-(R5-1)") (class "Default")
      (node (ref "C2") (pin "2") (pinfunction "2_2") (pintype "passive"))
      (node (ref "R5") (pin "P$1") (pinfunction "1_P$1") (pintype "passive"))
    )
    (net (code "39") (name "Net-(R9-1)") (class "Default")
      (node (ref "C4") (pin "1") (pinfunction "1_1") (pintype "passive"))
      (node (ref "R9") (pin "P$1") (pinfunction "1_P$1") (pintype "passive"))
    )
    (net (code "40") (name "Net-(R13-1)") (class "Default")
      (node (ref "C6") (pin "2") (pinfunction "2_2") (pintype "passive"))
      (node (ref "R13") (pin "P$1") (pinfunction "1_P$1") (pintype "passive"))
    )
    (net (code "41") (name "Net-(R16-1)") (class "Default")
      (node (ref "C8") (pin "2") (pinfunction "2_2") (pintype "passive"))
      (node (ref "R16") (pin "P$1") (pinfunction "1_P$1") (pintype "passive"))
    )
    (net (code "42") (name "Net-(R24-1)") (class "Default")
      (node (ref "C5") (pin "2") (pinfunction "2_2") (pintype "passive"))
      (node (ref "R24") (pin "P$1") (pinfunction "1_P$1") (pintype "passive"))
      (node (ref "R28") (pin "P$1") (pinfunction "1_P$1") (pintype "passive"))
      (node (ref "R34") (pin "P$1") (pinfunction "1_P$1") (pintype "passive"))
      (node (ref "R37") (pin "P$1") (pinfunction "1_P$1") (pintype "passive"))
    )
    (net (code "43") (name "Net-(R24-2)") (class "Default")
      (node (ref "C11") (pin "1") (pinfunction "1_1") (pintype "passive"))
      (node (ref "C12") (pin "2") (pinfunction "2_2") (pintype "passive"))
      (node (ref "R24") (pin "P$2") (pinfunction "2_P$2") (pintype "passive"))
      (node (ref "R25") (pin "P$2") (pinfunction "2_P$2") (pintype "passive"))
    )
    (net (code "44") (name "Net-(R27-1)") (class "Default")
      (node (ref "C13") (pin "2") (pinfunction "2_2") (pintype "passive"))
      (node (ref "R27") (pin "P$1") (pinfunction "1_P$1") (pintype "passive"))
    )
    (net (code "45") (name "Net-(R27-2)") (class "Default")
      (node (ref "R27") (pin "P$2") (pinfunction "2_P$2") (pintype "passive"))
      (node (ref "R32") (pin "2") (pinfunction "S_2") (pintype "passive"))
    )
    (net (code "46") (name "Net-(R28-2)") (class "Default")
      (node (ref "C14") (pin "1") (pinfunction "1_1") (pintype "passive"))
      (node (ref "C15") (pin "2") (pinfunction "2_2") (pintype "passive"))
      (node (ref "R28") (pin "P$2") (pinfunction "2_P$2") (pintype "passive"))
      (node (ref "R29") (pin "P$2") (pinfunction "2_P$2") (pintype "passive"))
    )
    (net (code "47") (name "Net-(R31-1)") (class "Default")
      (node (ref "C16") (pin "2") (pinfunction "2_2") (pintype "passive"))
      (node (ref "R31") (pin "P$1") (pinfunction "1_P$1") (pintype "passive"))
    )
    (net (code "48") (name "Net-(R31-2)") (class "Default")
      (node (ref "R31") (pin "P$2") (pinfunction "2_P$2") (pintype "passive"))
      (node (ref "R33") (pin "2") (pinfunction "S_2") (pintype "passive"))
    )
    (net (code "49") (name "Net-(R34-2)") (class "Default")
      (node (ref "C17") (pin "1") (pinfunction "1_1") (pintype "passive"))
      (node (ref "C18") (pin "2") (pinfunction "2_2") (pintype "passive"))
      (node (ref "R34") (pin "P$2") (pinfunction "2_P$2") (pintype "passive"))
      (node (ref "R35") (pin "P$2") (pinfunction "2_P$2") (pintype "passive"))
    )
    (net (code "50") (name "Net-(R37-2)") (class "Default")
      (node (ref "C19") (pin "1") (pinfunction "1_1") (pintype "passive"))
      (node (ref "C20") (pin "2") (pinfunction "2_2") (pintype "passive"))
      (node (ref "R37") (pin "P$2") (pinfunction "2_P$2") (pintype "passive"))
      (node (ref "R38") (pin "P$2") (pinfunction "2_P$2") (pintype "passive"))
    )
    (net (code "51") (name "Net-(R40-1)") (class "Default")
      (node (ref "C21") (pin "2") (pinfunction "2_2") (pintype "passive"))
      (node (ref "R40") (pin "P$1") (pinfunction "1_P$1") (pintype "passive"))
    )
    (net (code "52") (name "Net-(R40-2)") (class "Default")
      (node (ref "R40") (pin "P$2") (pinfunction "2_P$2") (pintype "passive"))
      (node (ref "R41") (pin "2") (pinfunction "S_2") (pintype "passive"))
    )
    (net (code "53") (name "Net-(R42-1)") (class "Default")
      (node (ref "C22") (pin "2") (pinfunction "2_2") (pintype "passive"))
      (node (ref "R42") (pin "P$1") (pinfunction "1_P$1") (pintype "passive"))
    )
    (net (code "54") (name "Net-(R42-2)") (class "Default")
      (node (ref "R42") (pin "P$2") (pinfunction "2_P$2") (pintype "passive"))
      (node (ref "R43") (pin "2") (pinfunction "S_2") (pintype "passive"))
    )
    (net (code "55") (name "VCC") (class "Default")
      (node (ref "C23") (pin "1") (pinfunction "+_1") (pintype "passive"))
      (node (ref "C25") (pin "1") (pinfunction "1_1") (pintype "passive"))
      (node (ref "IC1") (pin "4") (pinfunction "VCC_4") (pintype "power_in"))
      (node (ref "IC2") (pin "4") (pinfunction "VCC_4") (pintype "power_in"))
      (node (ref "IC3") (pin "8") (pinfunction "V+_8") (pintype "power_in"))
      (node (ref "IC7") (pin "4") (pinfunction "VCC_4") (pintype "power_in"))
      (node (ref "JP1") (pin "2") (pinfunction "2_2") (pintype "passive"))
      (node (ref "R14") (pin "P$2") (pinfunction "2_P$2") (pintype "passive"))
      (node (ref "R15") (pin "P$2") (pinfunction "2_P$2") (pintype "passive"))
    )
    (net (code "56") (name "VCC{slash}2") (class "Default")
      (node (ref "C24") (pin "1") (pinfunction "+_1") (pintype "passive"))
      (node (ref "IC1") (pin "10") (pinfunction "IN+_10") (pintype "input"))
      (node (ref "IC1") (pin "12") (pinfunction "IN+_12") (pintype "input"))
      (node (ref "IC1") (pin "3") (pinfunction "IN+_3") (pintype "input"))
      (node (ref "IC1") (pin "5") (pinfunction "IN+_5") (pintype "input"))
      (node (ref "IC2") (pin "10") (pinfunction "IN+_10") (pintype "input"))
      (node (ref "IC2") (pin "3") (pinfunction "IN+_3") (pintype "input"))
      (node (ref "IC2") (pin "5") (pinfunction "IN+_5") (pintype "input"))
      (node (ref "IC3") (pin "5") (pinfunction "+IN_5") (pintype "input"))
      (node (ref "IC7") (pin "10") (pinfunction "IN+_10") (pintype "input"))
      (node (ref "IC7") (pin "12") (pinfunction "IN+_12") (pintype "input"))
      (node (ref "R1") (pin "P$2") (pinfunction "2_P$2") (pintype "passive"))
      (node (ref "R14") (pin "P$1") (pinfunction "1_P$1") (pintype "passive"))
      (node (ref "R2") (pin "P$1") (pinfunction "1_P$1") (pintype "passive"))
      (node (ref "R4") (pin "P$1") (pinfunction "1_P$1") (pintype "passive"))
      (node (ref "R45") (pin "P$2") (pinfunction "2_P$2") (pintype "passive"))
    )
    (net (code "57") (name "XLR_HOT") (class "Default")
      (node (ref "R18") (pin "P$2") (pinfunction "2_P$2") (pintype "passive"))
      (node (ref "R19") (pin "P$2") (pinfunction "2_P$2") (pintype "passive"))
    )
    (net (code "58") (name "XLR_NEG") (class "Default")
      (node (ref "R22") (pin "P$2") (pinfunction "2_P$2") (pintype "passive"))
      (node (ref "R23") (pin "P$2") (pinfunction "2_P$2") (pintype "passive"))
    )
  )
)
